# GTM_BallGrippersDiodesConnectors.net
KiCad netlist of a schematic drawn in Altium Designer
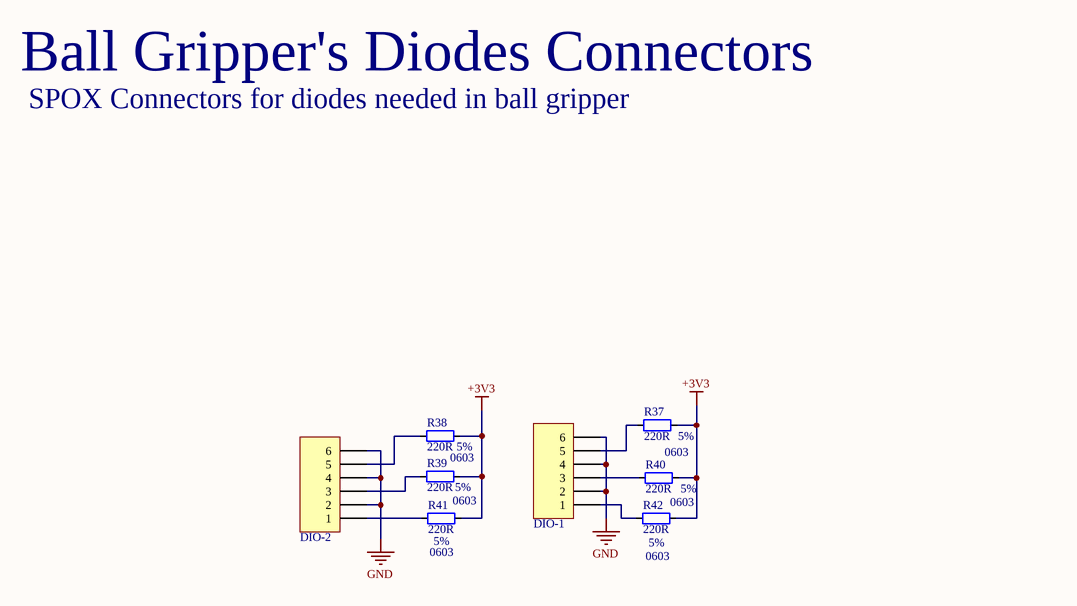
[diagram p0: GTM_BallGrippersDiodesConnectors.SchDoc]

(export (version "E")
  (design (tool "Eeschema 10.0.6"))
  (components
    (comp (ref "DIO-1")
      (value "HDR1X6")
      (footprint "Molex SPOX Horizontal 6 Circuits")
      (description "Header, 6-Pin")
      (fields (field (name "PUBLISHER") "Altium Limited"))
      (libsource (lib "Library_Altium_KNR") (part "HDR1X6"))
    )
    (comp (ref "DIO-2")
      (value "HDR1X6")
      (footprint "Molex SPOX Horizontal 6 Circuits")
      (description "Header, 6-Pin")
      (fields (field (name "PUBLISHER") "Altium Limited"))
      (libsource (lib "Library_Altium_KNR") (part "HDR1X6"))
    )
    (comp (ref "R37")
      (value "220R")
      (footprint "0603")
      (description "Resistior")
      (fields (field (name "TOLERANCE") "5%") (field (name "PACKAGE") "0603"))
      (libsource (lib "Library_Altium_KNR") (part "RES"))
    )
    (comp (ref "R38")
      (value "220R")
      (footprint "0603")
      (description "Resistior")
      (fields (field (name "TOLERANCE") "5%") (field (name "PACKAGE") "0603"))
      (libsource (lib "Library_Altium_KNR") (part "RES"))
    )
    (comp (ref "R39")
      (value "220R")
      (footprint "0603")
      (description "Resistior")
      (fields (field (name "TOLERANCE") "5%") (field (name "PACKAGE") "0603"))
      (libsource (lib "Library_Altium_KNR") (part "RES"))
    )
    (comp (ref "R40")
      (value "220R")
      (footprint "0603")
      (description "Resistior")
      (fields (field (name "TOLERANCE") "5%") (field (name "PACKAGE") "0603"))
      (libsource (lib "Library_Altium_KNR") (part "RES"))
    )
    (comp (ref "R41")
      (value "220R")
      (footprint "0603")
      (description "Resistior")
      (fields (field (name "TOLERANCE") "5%") (field (name "PACKAGE") "0603"))
      (libsource (lib "Library_Altium_KNR") (part "RES"))
    )
    (comp (ref "R42")
      (value "220R")
      (footprint "0603")
      (description "Resistior")
      (fields (field (name "TOLERANCE") "5%") (field (name "PACKAGE") "0603"))
      (libsource (lib "Library_Altium_KNR") (part "RES"))
    )
  )
  (nets
    (net (code "1") (name "+3V3") (class "Default")
      (node (ref "R37") (pin "1") (pinfunction "1_1") (pintype "passive"))
      (node (ref "R38") (pin "1") (pinfunction "1_1") (pintype "passive"))
      (node (ref "R39") (pin "1") (pinfunction "1_1") (pintype "passive"))
      (node (ref "R40") (pin "1") (pinfunction "1_1") (pintype "passive"))
      (node (ref "R41") (pin "1") (pinfunction "1_1") (pintype "passive"))
      (node (ref "R42") (pin "1") (pinfunction "1_1") (pintype "passive"))
    )
    (net (code "2") (name "GND") (class "Default")
      (node (ref "DIO-1") (pin "2") (pinfunction "2_2") (pintype "passive"))
      (node (ref "DIO-1") (pin "4") (pinfunction "4_4") (pintype "passive"))
      (node (ref "DIO-1") (pin "6") (pinfunction "6_6") (pintype "passive"))
      (node (ref "DIO-2") (pin "2") (pinfunction "2_2") (pintype "passive"))
      (node (ref "DIO-2") (pin "4") (pinfunction "4_4") (pintype "passive"))
      (node (ref "DIO-2") (pin "6") (pinfunction "6_6") (pintype "passive"))
    )
    (net (code "3") (name "Net-(DIO-1-Pad1)") (class "Default")
      (node (ref "DIO-1") (pin "1") (pinfunction "1_1") (pintype "passive"))
      (node (ref "R42") (pin "2") (pinfunction "2_2") (pintype "passive"))
    )
    (net (code "4") (name "Net-(DIO-1-Pad3)") (class "Default")
      (node (ref "DIO-1") (pin "3") (pinfunction "3_3") (pintype "passive"))
      (node (ref "R40") (pin "2") (pinfunction "2_2") (pintype "passive"))
    )
    (net (code "5") (name "Net-(DIO-1-Pad5)") (class "Default")
      (node (ref "DIO-1") (pin "5") (pinfunction "5_5") (pintype "passive"))
      (node (ref "R37") (pin "2") (pinfunction "2_2") (pintype "passive"))
    )
    (net (code "6") (name "Net-(DIO-2-Pad1)") (class "Default")
      (node (ref "DIO-2") (pin "1") (pinfunction "1_1") (pintype "passive"))
      (node (ref "R41") (pin "2") (pinfunction "2_2") (pintype "passive"))
    )
    (net (code "7") (name "Net-(DIO-2-Pad3)") (class "Default")
      (node (ref "DIO-2") (pin "3") (pinfunction "3_3") (pintype "passive"))
      (node (ref "R39") (pin "2") (pinfunction "2_2") (pintype "passive"))
    )
    (net (code "8") (name "Net-(DIO-2-Pad5)") (class "Default")
      (node (ref "DIO-2") (pin "5") (pinfunction "5_5") (pintype "passive"))
      (node (ref "R38") (pin "2") (pinfunction "2_2") (pintype "passive"))
    )
  )
)
